# design.net
KiCad netlist of a schematic drawn in Altium Designer
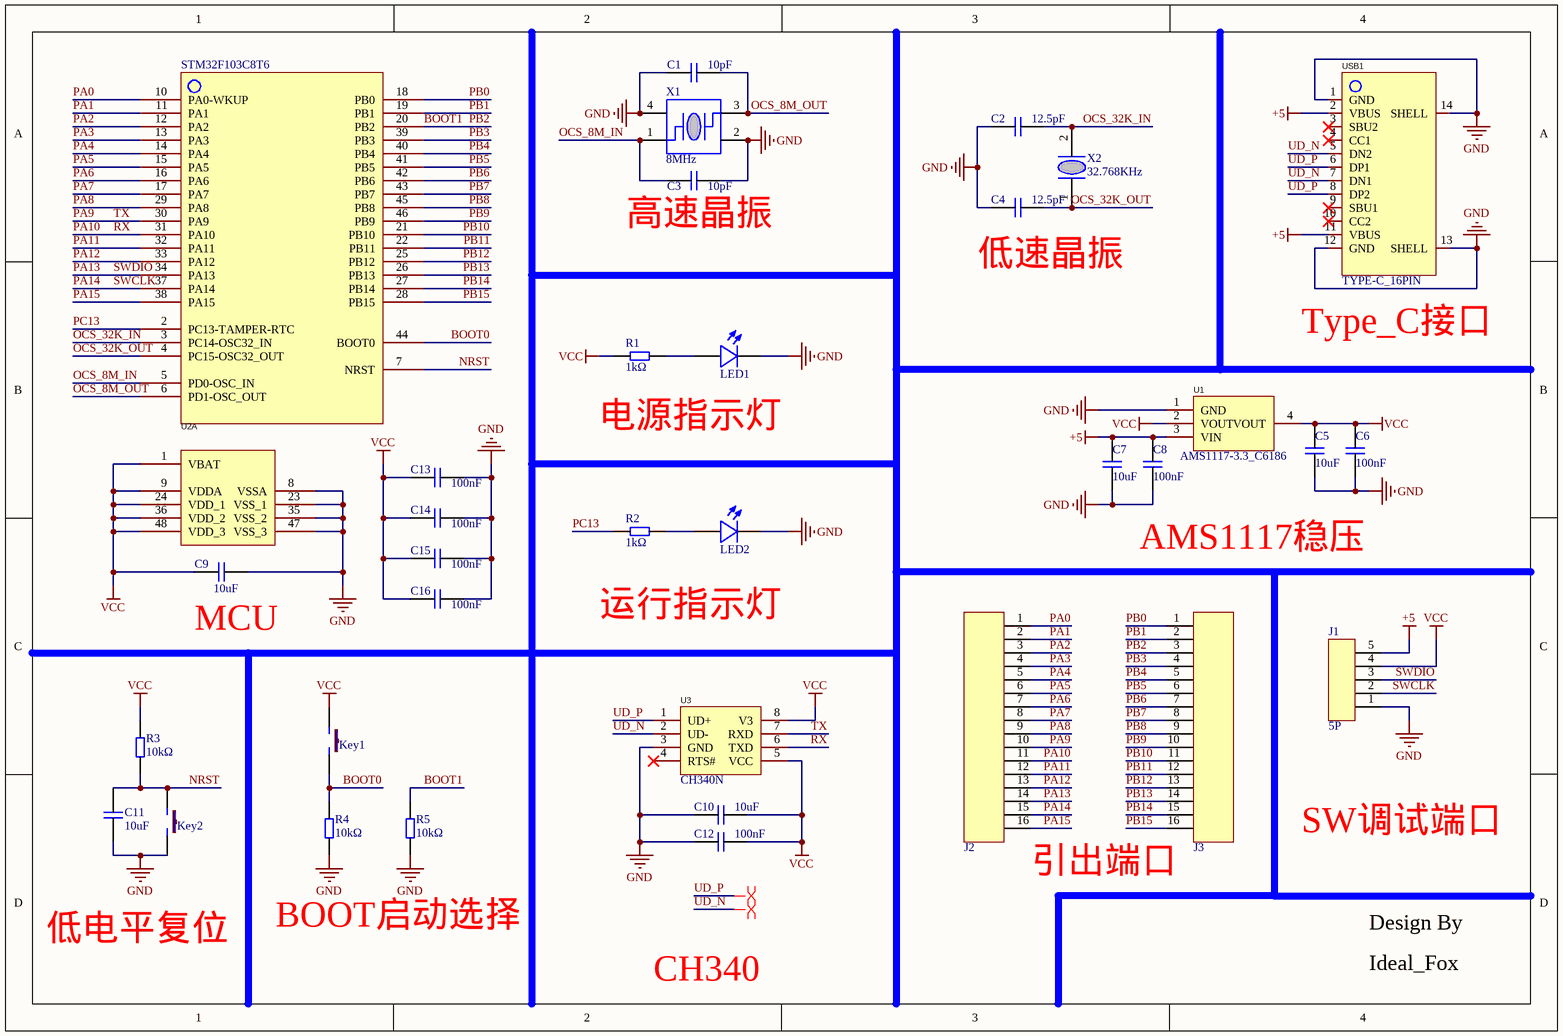
[diagram p0: 原理图.SchDoc]

(export (version "E")
  (design (tool "Eeschema 10.0.6"))
  (components
    (comp (ref "C1") (value "10pF") (footprint "C0603") (libsource (lib "Schlib") (part "CAP")))
    (comp (ref "C2") (value "12.5pF") (footprint "C0603") (libsource (lib "Schlib") (part "CAP")))
    (comp (ref "C3") (value "10pF") (footprint "C0603") (libsource (lib "Schlib") (part "CAP")))
    (comp (ref "C4") (value "12.5pF") (footprint "C0603") (libsource (lib "Schlib") (part "CAP")))
    (comp (ref "C5") (value "10uF") (footprint "C0603") (libsource (lib "Schlib") (part "CAP")))
    (comp (ref "C6") (value "100nF") (footprint "C0603") (libsource (lib "Schlib") (part "CAP")))
    (comp (ref "C7") (value "10uF") (footprint "C0603") (libsource (lib "Schlib") (part "CAP")))
    (comp (ref "C8") (value "100nF") (footprint "C0603") (libsource (lib "Schlib") (part "CAP")))
    (comp (ref "C9") (value "10uF") (footprint "C0603") (libsource (lib "Schlib") (part "CAP")))
    (comp (ref "C10") (value "10uF") (footprint "C0603") (libsource (lib "Schlib") (part "CAP")))
    (comp (ref "C11") (value "10uF") (footprint "C0603") (libsource (lib "Schlib") (part "CAP")))
    (comp (ref "C12") (value "100nF") (footprint "C0603") (libsource (lib "Schlib") (part "CAP")))
    (comp (ref "C13") (value "100nF") (footprint "C0603") (libsource (lib "Schlib") (part "CAP")))
    (comp (ref "C14") (value "100nF") (footprint "C0603") (libsource (lib "Schlib") (part "CAP")))
    (comp (ref "C15") (value "100nF") (footprint "C0603") (libsource (lib "Schlib") (part "CAP")))
    (comp (ref "C16") (value "100nF") (footprint "C0603") (libsource (lib "Schlib") (part "CAP")))
    (comp (ref "J1") (value "5P") (footprint "5P-P2.54") (libsource (lib "Schlib") (part "5P")))
    (comp (ref "J2") (value "2x10P") (footprint "2X10P-P2.54") (libsource (lib "") (part "2x10P_1")))
    (comp (ref "J3") (value "2x10P") (footprint "2X10P-P2.54") (libsource (lib "Schlib") (part "2x10P")))
    (comp (ref "Key1") (value "KEY") (footprint "SW_2P") (libsource (lib "Schlib") (part "KEY")))
    (comp (ref "Key2") (value "KEY") (footprint "SW_2P") (libsource (lib "Schlib") (part "KEY")))
    (comp (ref "LED1") (value "LED_R") (footprint "LED0805") (libsource (lib "Schlib") (part "LED")))
    (comp (ref "LED2") (value "LED_R") (footprint "LED0805") (libsource (lib "Schlib") (part "LED")))
    (comp (ref "R1") (value "1kΩ") (footprint "R0603") (libsource (lib "Schlib") (part "RES")))
    (comp (ref "R2") (value "1kΩ") (footprint "R0603") (libsource (lib "Schlib") (part "RES")))
    (comp (ref "R3") (value "10kΩ") (footprint "R0603") (libsource (lib "Schlib") (part "RES")))
    (comp (ref "R4") (value "10kΩ") (footprint "R0603") (libsource (lib "Schlib") (part "RES")))
    (comp (ref "R5") (value "10kΩ") (footprint "R0603") (libsource (lib "Schlib") (part "RES")))
    (comp (ref "U1")
      (value "AMS1117-3.3_C6186")
      (footprint "SOT-223-3_L6.5-W3.4-P2.30-LS7.0-BR")
      (fields (field (name "MANUFACTURER") "AMS") (field (name "MANUFACTURER PART") "AMS1117-3.3"))
      (libsource (lib "Schlib") (part "AMS1117-3.3"))
    )
    (comp (ref "U2")
      (value "STM32F103C8T6")
      (footprint "STM32F103C8T6")
      (fields (field (name "MANUFACTURER") "ST(意法半导体)"))
      (libsource (lib "Schlib") (part "STM32F103C8T6"))
    )
    (comp (ref "U3")
      (value "CH340N")
      (footprint "SOP-8_L4.9-W3.9-P1.27-LS6.0-BL")
      (fields (field (name "MANUFACTURER") "WCH(南京沁恒)"))
      (libsource (lib "Schlib") (part "CH340N"))
    )
    (comp (ref "USB1")
      (value "TYPE-C_16PIN")
      (footprint "USB-C-SMD_TYPE-C-16PIN")
      (fields
        (field (name "MANUFACTURER") "SHOU HAN(首韩)")
        (field (name "MANUFACTURER PART") "TYPE-C 16PIN 2MD(073)")
      )
      (libsource (lib "Schlib") (part "TYPE-C_16PIN"))
    )
    (comp (ref "X1") (value "8MHz") (footprint "SMD_4P_5032") (libsource (lib "Schlib") (part "晶振")))
    (comp (ref "X2") (value "32.768KHz") (footprint "SMD_2P_3215") (libsource (lib "Schlib") (part "晶振_1")))
  )
  (nets
    (net (code "1") (name "+5") (class "Default")
      (node (ref "C7") (pin "2") (pinfunction "2_2") (pintype "passive"))
      (node (ref "C8") (pin "2") (pinfunction "2_2") (pintype "passive"))
      (node (ref "J1") (pin "5") (pinfunction "5_5") (pintype "passive"))
      (node (ref "U1") (pin "3") (pinfunction "VIN_3") (pintype "passive"))
      (node (ref "USB1") (pin "11") (pinfunction "VBUS_11") (pintype "passive"))
      (node (ref "USB1") (pin "2") (pinfunction "VBUS_2") (pintype "passive"))
    )
    (net (code "2") (name "/BOOT0") (class "Default")
      (node (ref "Key1") (pin "2") (pinfunction "2_2") (pintype "passive"))
      (node (ref "R4") (pin "1") (pinfunction "1_1") (pintype "passive"))
      (node (ref "U2") (pin "44") (pinfunction "BOOT0_44") (pintype "passive"))
    )
    (net (code "3") (name "/BOOT1") (class "Default")
      (node (ref "J3") (pin "3") (pinfunction "3_3") (pintype "passive"))
      (node (ref "R5") (pin "1") (pinfunction "1_1") (pintype "passive"))
      (node (ref "U2") (pin "20") (pinfunction "PB2_20") (pintype "passive"))
    )
    (net (code "4") (name "/NRST") (class "Default")
      (node (ref "C11") (pin "1") (pinfunction "1_1") (pintype "passive"))
      (node (ref "Key2") (pin "1") (pinfunction "1_1") (pintype "passive"))
      (node (ref "R3") (pin "2") (pinfunction "2_2") (pintype "passive"))
      (node (ref "U2") (pin "7") (pinfunction "NRST_7") (pintype "passive"))
    )
    (net (code "5") (name "/OCS_8M_IN") (class "Default")
      (node (ref "C3") (pin "1") (pinfunction "1_1") (pintype "passive"))
      (node (ref "U2") (pin "5") (pinfunction "PD0-OSC_IN_5") (pintype "passive"))
      (node (ref "X1") (pin "1") (pinfunction "1_1") (pintype "passive"))
    )
    (net (code "6") (name "/OCS_8M_OUT") (class "Default")
      (node (ref "C1") (pin "2") (pinfunction "2_2") (pintype "passive"))
      (node (ref "U2") (pin "6") (pinfunction "PD1-OSC_OUT_6") (pintype "passive"))
      (node (ref "X1") (pin "3") (pinfunction "3_3") (pintype "passive"))
    )
    (net (code "7") (name "/OCS_32K_IN") (class "Default")
      (node (ref "C2") (pin "2") (pinfunction "2_2") (pintype "passive"))
      (node (ref "U2") (pin "3") (pinfunction "PC14-OSC32_IN_3") (pintype "passive"))
      (node (ref "X2") (pin "2") (pinfunction "2_2") (pintype "passive"))
    )
    (net (code "8") (name "/OCS_32K_OUT") (class "Default")
      (node (ref "C4") (pin "2") (pinfunction "2_2") (pintype "passive"))
      (node (ref "U2") (pin "4") (pinfunction "PC15-OSC32_OUT_4") (pintype "passive"))
      (node (ref "X2") (pin "1") (pinfunction "1_1") (pintype "passive"))
    )
    (net (code "9") (name "/PA0") (class "Default")
      (node (ref "J2") (pin "1") (pinfunction "1_1") (pintype "passive"))
      (node (ref "U2") (pin "10") (pinfunction "PA0-WKUP_10") (pintype "passive"))
    )
    (net (code "10") (name "/PA1") (class "Default")
      (node (ref "J2") (pin "2") (pinfunction "2_2") (pintype "passive"))
      (node (ref "U2") (pin "11") (pinfunction "PA1_11") (pintype "passive"))
    )
    (net (code "11") (name "/PA2") (class "Default")
      (node (ref "J2") (pin "3") (pinfunction "3_3") (pintype "passive"))
      (node (ref "U2") (pin "12") (pinfunction "PA2_12") (pintype "passive"))
    )
    (net (code "12") (name "/PA3") (class "Default")
      (node (ref "J2") (pin "4") (pinfunction "4_4") (pintype "passive"))
      (node (ref "U2") (pin "13") (pinfunction "PA3_13") (pintype "passive"))
    )
    (net (code "13") (name "/PA4") (class "Default")
      (node (ref "J2") (pin "5") (pinfunction "5_5") (pintype "passive"))
      (node (ref "U2") (pin "14") (pinfunction "PA4_14") (pintype "passive"))
    )
    (net (code "14") (name "/PA5") (class "Default")
      (node (ref "J2") (pin "6") (pinfunction "6_6") (pintype "passive"))
      (node (ref "U2") (pin "15") (pinfunction "PA5_15") (pintype "passive"))
    )
    (net (code "15") (name "/PA6") (class "Default")
      (node (ref "J2") (pin "7") (pinfunction "7_7") (pintype "passive"))
      (node (ref "U2") (pin "16") (pinfunction "PA6_16") (pintype "passive"))
    )
    (net (code "16") (name "/PA7") (class "Default")
      (node (ref "J2") (pin "8") (pinfunction "8_8") (pintype "passive"))
      (node (ref "U2") (pin "17") (pinfunction "PA7_17") (pintype "passive"))
    )
    (net (code "17") (name "/PA8") (class "Default")
      (node (ref "J2") (pin "9") (pinfunction "9_9") (pintype "passive"))
      (node (ref "U2") (pin "29") (pinfunction "PA8_29") (pintype "passive"))
    )
    (net (code "18") (name "/PA9") (class "Default")
      (node (ref "J2") (pin "10") (pinfunction "10_10") (pintype "passive"))
      (node (ref "U2") (pin "30") (pinfunction "PA9_30") (pintype "passive"))
      (node (ref "U3") (pin "7") (pinfunction "RXD_7") (pintype "passive"))
    )
    (net (code "19") (name "/PA10") (class "Default")
      (node (ref "J2") (pin "11") (pinfunction "11_11") (pintype "passive"))
      (node (ref "U2") (pin "31") (pinfunction "PA10_31") (pintype "passive"))
      (node (ref "U3") (pin "6") (pinfunction "TXD_6") (pintype "passive"))
    )
    (net (code "20") (name "/PA11") (class "Default")
      (node (ref "J2") (pin "12") (pinfunction "12_12") (pintype "passive"))
      (node (ref "U2") (pin "32") (pinfunction "PA11_32") (pintype "passive"))
    )
    (net (code "21") (name "/PA12") (class "Default")
      (node (ref "J2") (pin "13") (pinfunction "13_13") (pintype "passive"))
      (node (ref "U2") (pin "33") (pinfunction "PA12_33") (pintype "passive"))
    )
    (net (code "22") (name "/PA13") (class "Default")
      (node (ref "J1") (pin "3") (pinfunction "3_3") (pintype "passive"))
      (node (ref "J2") (pin "14") (pinfunction "14_14") (pintype "passive"))
      (node (ref "U2") (pin "34") (pinfunction "PA13_34") (pintype "passive"))
    )
    (net (code "23") (name "/PA14") (class "Default")
      (node (ref "J1") (pin "2") (pinfunction "2_2") (pintype "passive"))
      (node (ref "J2") (pin "15") (pinfunction "15_15") (pintype "passive"))
      (node (ref "U2") (pin "37") (pinfunction "PA14_37") (pintype "passive"))
    )
    (net (code "24") (name "/PA15") (class "Default")
      (node (ref "J2") (pin "16") (pinfunction "16_16") (pintype "passive"))
      (node (ref "U2") (pin "38") (pinfunction "PA15_38") (pintype "passive"))
    )
    (net (code "25") (name "/PB0") (class "Default")
      (node (ref "J3") (pin "1") (pinfunction "1_1") (pintype "passive"))
      (node (ref "U2") (pin "18") (pinfunction "PB0_18") (pintype "passive"))
    )
    (net (code "26") (name "/PB1") (class "Default")
      (node (ref "J3") (pin "2") (pinfunction "2_2") (pintype "passive"))
      (node (ref "U2") (pin "19") (pinfunction "PB1_19") (pintype "passive"))
    )
    (net (code "27") (name "/PB3") (class "Default")
      (node (ref "J3") (pin "4") (pinfunction "4_4") (pintype "passive"))
      (node (ref "U2") (pin "39") (pinfunction "PB3_39") (pintype "passive"))
    )
    (net (code "28") (name "/PB4") (class "Default")
      (node (ref "J3") (pin "5") (pinfunction "5_5") (pintype "passive"))
      (node (ref "U2") (pin "40") (pinfunction "PB4_40") (pintype "passive"))
    )
    (net (code "29") (name "/PB5") (class "Default")
      (node (ref "J3") (pin "6") (pinfunction "6_6") (pintype "passive"))
      (node (ref "U2") (pin "41") (pinfunction "PB5_41") (pintype "passive"))
    )
    (net (code "30") (name "/PB6") (class "Default")
      (node (ref "J3") (pin "7") (pinfunction "7_7") (pintype "passive"))
      (node (ref "U2") (pin "42") (pinfunction "PB6_42") (pintype "passive"))
    )
    (net (code "31") (name "/PB7") (class "Default")
      (node (ref "J3") (pin "8") (pinfunction "8_8") (pintype "passive"))
      (node (ref "U2") (pin "43") (pinfunction "PB7_43") (pintype "passive"))
    )
    (net (code "32") (name "/PB8") (class "Default")
      (node (ref "J3") (pin "9") (pinfunction "9_9") (pintype "passive"))
      (node (ref "U2") (pin "45") (pinfunction "PB8_45") (pintype "passive"))
    )
    (net (code "33") (name "/PB9") (class "Default")
      (node (ref "J3") (pin "10") (pinfunction "10_10") (pintype "passive"))
      (node (ref "U2") (pin "46") (pinfunction "PB9_46") (pintype "passive"))
    )
    (net (code "34") (name "/PB10") (class "Default")
      (node (ref "J3") (pin "11") (pinfunction "11_11") (pintype "passive"))
      (node (ref "U2") (pin "21") (pinfunction "PB10_21") (pintype "passive"))
    )
    (net (code "35") (name "/PB11") (class "Default")
      (node (ref "J3") (pin "12") (pinfunction "12_12") (pintype "passive"))
      (node (ref "U2") (pin "22") (pinfunction "PB11_22") (pintype "passive"))
    )
    (net (code "36") (name "/PB12") (class "Default")
      (node (ref "J3") (pin "13") (pinfunction "13_13") (pintype "passive"))
      (node (ref "U2") (pin "25") (pinfunction "PB12_25") (pintype "passive"))
    )
    (net (code "37") (name "/PB13") (class "Default")
      (node (ref "J3") (pin "14") (pinfunction "14_14") (pintype "passive"))
      (node (ref "U2") (pin "26") (pinfunction "PB13_26") (pintype "passive"))
    )
    (net (code "38") (name "/PB14") (class "Default")
      (node (ref "J3") (pin "15") (pinfunction "15_15") (pintype "passive"))
      (node (ref "U2") (pin "27") (pinfunction "PB14_27") (pintype "passive"))
    )
    (net (code "39") (name "/PB15") (class "Default")
      (node (ref "J3") (pin "16") (pinfunction "16_16") (pintype "passive"))
      (node (ref "U2") (pin "28") (pinfunction "PB15_28") (pintype "passive"))
    )
    (net (code "40") (name "/PC13") (class "Default")
      (node (ref "R2") (pin "1") (pinfunction "1_1") (pintype "passive"))
      (node (ref "U2") (pin "2") (pinfunction "PC13-TAMPER-RTC_2") (pintype "passive"))
    )
    (net (code "41") (name "/UD_N") (class "Default")
      (node (ref "U3") (pin "2") (pinfunction "UD-_2") (pintype "passive"))
      (node (ref "USB1") (pin "5") (pinfunction "DN2_5") (pintype "passive"))
      (node (ref "USB1") (pin "7") (pinfunction "DN1_7") (pintype "passive"))
    )
    (net (code "42") (name "/UD_P") (class "Default")
      (node (ref "U3") (pin "1") (pinfunction "UD+_1") (pintype "passive"))
      (node (ref "USB1") (pin "6") (pinfunction "DP1_6") (pintype "passive"))
      (node (ref "USB1") (pin "8") (pinfunction "DP2_8") (pintype "passive"))
    )
    (net (code "43") (name "GND") (class "Default")
      (node (ref "C1") (pin "1") (pinfunction "1_1") (pintype "passive"))
      (node (ref "C10") (pin "1") (pinfunction "1_1") (pintype "passive"))
      (node (ref "C11") (pin "2") (pinfunction "2_2") (pintype "passive"))
      (node (ref "C12") (pin "1") (pinfunction "1_1") (pintype "passive"))
      (node (ref "C13") (pin "1") (pinfunction "1_1") (pintype "passive"))
      (node (ref "C14") (pin "1") (pinfunction "1_1") (pintype "passive"))
      (node (ref "C15") (pin "1") (pinfunction "1_1") (pintype "passive"))
      (node (ref "C16") (pin "1") (pinfunction "1_1") (pintype "passive"))
      (node (ref "C2") (pin "1") (pinfunction "1_1") (pintype "passive"))
      (node (ref "C3") (pin "2") (pinfunction "2_2") (pintype "passive"))
      (node (ref "C4") (pin "1") (pinfunction "1_1") (pintype "passive"))
      (node (ref "C5") (pin "1") (pinfunction "1_1") (pintype "passive"))
      (node (ref "C6") (pin "1") (pinfunction "1_1") (pintype "passive"))
      (node (ref "C7") (pin "1") (pinfunction "1_1") (pintype "passive"))
      (node (ref "C8") (pin "1") (pinfunction "1_1") (pintype "passive"))
      (node (ref "C9") (pin "2") (pinfunction "2_2") (pintype "passive"))
      (node (ref "J1") (pin "1") (pinfunction "1_1") (pintype "passive"))
      (node (ref "Key2") (pin "2") (pinfunction "2_2") (pintype "passive"))
      (node (ref "LED1") (pin "2") (pinfunction "2_2") (pintype "passive"))
      (node (ref "LED2") (pin "2") (pinfunction "2_2") (pintype "passive"))
      (node (ref "R4") (pin "2") (pinfunction "2_2") (pintype "passive"))
      (node (ref "R5") (pin "2") (pinfunction "2_2") (pintype "passive"))
      (node (ref "U1") (pin "1") (pinfunction "GND_1") (pintype "passive"))
      (node (ref "U2") (pin "23") (pinfunction "VSS_1_23") (pintype "passive"))
      (node (ref "U2") (pin "35") (pinfunction "VSS_2_35") (pintype "passive"))
      (node (ref "U2") (pin "47") (pinfunction "VSS_3_47") (pintype "passive"))
      (node (ref "U2") (pin "8") (pinfunction "VSSA_8") (pintype "passive"))
      (node (ref "U3") (pin "3") (pinfunction "GND_3") (pintype "passive"))
      (node (ref "USB1") (pin "1") (pinfunction "GND_1") (pintype "passive"))
      (node (ref "USB1") (pin "12") (pinfunction "GND_12") (pintype "passive"))
      (node (ref "USB1") (pin "13") (pinfunction "SHELL_13") (pintype "passive"))
      (node (ref "USB1") (pin "14") (pinfunction "SHELL_14") (pintype "passive"))
      (node (ref "X1") (pin "2") (pinfunction "2_2") (pintype "passive"))
      (node (ref "X1") (pin "4") (pinfunction "4_4") (pintype "passive"))
    )
    (net (code "44") (name "Net-(LED1-Pad1)") (class "Default")
      (node (ref "LED1") (pin "1") (pinfunction "1_1") (pintype "passive"))
      (node (ref "R1") (pin "2") (pinfunction "2_2") (pintype "passive"))
    )
    (net (code "45") (name "Net-(LED2-Pad1)") (class "Default")
      (node (ref "LED2") (pin "1") (pinfunction "1_1") (pintype "passive"))
      (node (ref "R2") (pin "2") (pinfunction "2_2") (pintype "passive"))
    )
    (net (code "46") (name "VCC") (class "Default")
      (node (ref "C10") (pin "2") (pinfunction "2_2") (pintype "passive"))
      (node (ref "C12") (pin "2") (pinfunction "2_2") (pintype "passive"))
      (node (ref "C13") (pin "2") (pinfunction "2_2") (pintype "passive"))
      (node (ref "C14") (pin "2") (pinfunction "2_2") (pintype "passive"))
      (node (ref "C15") (pin "2") (pinfunction "2_2") (pintype "passive"))
      (node (ref "C16") (pin "2") (pinfunction "2_2") (pintype "passive"))
      (node (ref "C5") (pin "2") (pinfunction "2_2") (pintype "passive"))
      (node (ref "C6") (pin "2") (pinfunction "2_2") (pintype "passive"))
      (node (ref "C9") (pin "1") (pinfunction "1_1") (pintype "passive"))
      (node (ref "J1") (pin "4") (pinfunction "4_4") (pintype "passive"))
      (node (ref "Key1") (pin "1") (pinfunction "1_1") (pintype "passive"))
      (node (ref "R1") (pin "1") (pinfunction "1_1") (pintype "passive"))
      (node (ref "R3") (pin "1") (pinfunction "1_1") (pintype "passive"))
      (node (ref "U1") (pin "2") (pinfunction "VOUT_2") (pintype "passive"))
      (node (ref "U1") (pin "4") (pinfunction "VOUT_4") (pintype "passive"))
      (node (ref "U2") (pin "1") (pinfunction "VBAT_1") (pintype "passive"))
      (node (ref "U2") (pin "24") (pinfunction "VDD_1_24") (pintype "passive"))
      (node (ref "U2") (pin "36") (pinfunction "VDD_2_36") (pintype "passive"))
      (node (ref "U2") (pin "48") (pinfunction "VDD_3_48") (pintype "passive"))
      (node (ref "U2") (pin "9") (pinfunction "VDDA_9") (pintype "passive"))
      (node (ref "U3") (pin "5") (pinfunction "VCC_5") (pintype "passive"))
      (node (ref "U3") (pin "8") (pinfunction "V3_8") (pintype "passive"))
    )
    (net (code "47") (name "unconnected-(U3-RTS#-Pad4)") (class "Default")
      (node (ref "U3") (pin "4") (pinfunction "RTS#_4") (pintype "passive+no_connect"))
    )
    (net (code "48") (name "unconnected-(USB1-CC1-Pad4)") (class "Default")
      (node (ref "USB1") (pin "4") (pinfunction "CC1_4") (pintype "passive+no_connect"))
    )
    (net (code "49") (name "unconnected-(USB1-CC2-Pad10)") (class "Default")
      (node (ref "USB1") (pin "10") (pinfunction "CC2_10") (pintype "passive+no_connect"))
    )
    (net (code "50") (name "unconnected-(USB1-SBU1-Pad9)") (class "Default")
      (node (ref "USB1") (pin "9") (pinfunction "SBU1_9") (pintype "passive+no_connect"))
    )
    (net (code "51") (name "unconnected-(USB1-SBU2-Pad3)") (class "Default")
      (node (ref "USB1") (pin "3") (pinfunction "SBU2_3") (pintype "passive+no_connect"))
    )
  )
)
